# JTAG20M-STLV2.net
KiCad netlist of a schematic drawn in EAGLE
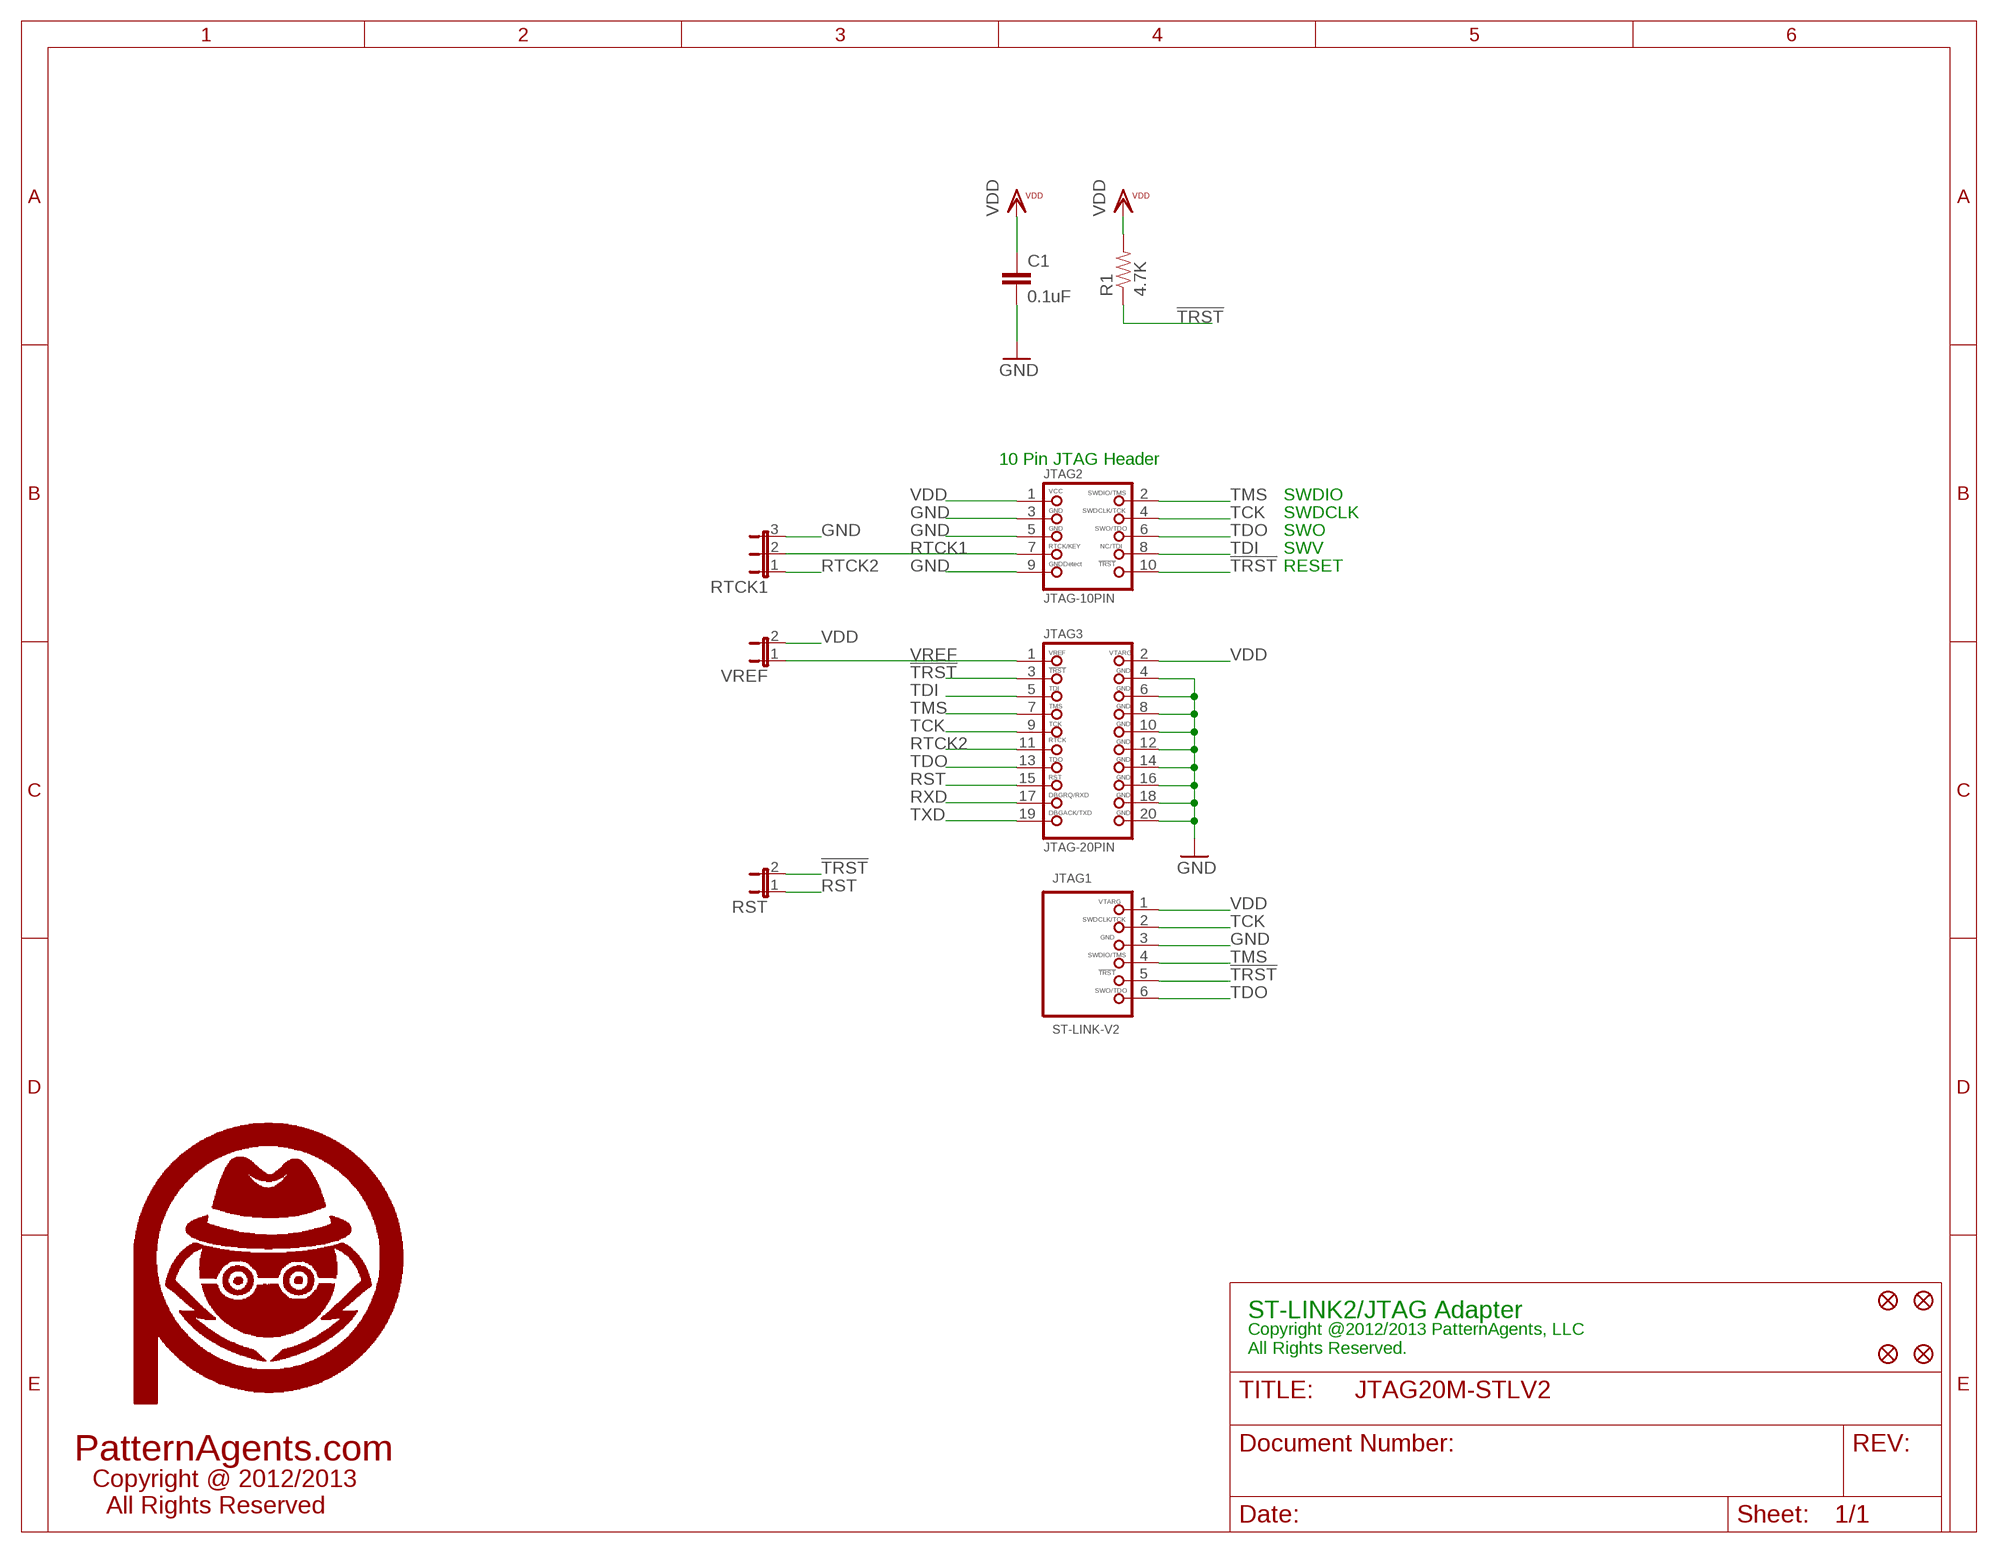
[diagram p0: schematic, sheet 1]

(export (version "E")
  (design (tool "Eeschema 10.0.6"))
  (components
    (comp (ref "C1")
      (value "0.1uF")
      (footprint "eagle-import:0603-CAP")
      (libsource (lib "eagle-import") (part "CAP0603-CAP"))
    )
    (comp (ref "FID1")
      (value "FIDUCIAL1.5X3")
      (footprint "eagle-import:FIDUCIAL-1.5X3")
      (libsource (lib "eagle-import") (part "FIDUCIAL1.5X3"))
    )
    (comp (ref "FID2")
      (value "FIDUCIAL1.5X3")
      (footprint "eagle-import:FIDUCIAL-1.5X3")
      (libsource (lib "eagle-import") (part "FIDUCIAL1.5X3"))
    )
    (comp (ref "FID3")
      (value "FIDUCIAL1.5X3")
      (footprint "eagle-import:FIDUCIAL-1.5X3")
      (libsource (lib "eagle-import") (part "FIDUCIAL1.5X3"))
    )
    (comp (ref "FID4")
      (value "FIDUCIAL1.5X3")
      (footprint "eagle-import:FIDUCIAL-1.5X3")
      (libsource (lib "eagle-import") (part "FIDUCIAL1.5X3"))
    )
    (comp (ref "JTAG1")
      (value "ST-LINK-V2")
      (footprint "eagle-import:1X06_2.54MM_PTH")
      (libsource (lib "eagle-import") (part "ST-LINK-V2"))
    )
    (comp (ref "JTAG2")
      (value "JTAG-10PIN")
      (footprint "eagle-import:2X05_1.27MM_SMT")
      (libsource (lib "eagle-import") (part "JTAG-10PINSMD"))
    )
    (comp (ref "JTAG3")
      (value "JTAG-20PIN")
      (footprint "eagle-import:2X10_2.54MM_PTH")
      (libsource (lib "eagle-import") (part "JTAG-20PIN"))
    )
    (comp (ref "R1")
      (value "4.7K")
      (footprint "eagle-import:0603-RES")
      (libsource (lib "eagle-import") (part "RESISTOR_SFE0603-RES"))
    )
    (comp (ref "RST")
      (value "JUMPER2")
      (footprint "eagle-import:JUMPER2")
      (libsource (lib "eagle-import") (part "JUMPER2"))
    )
    (comp (ref "RTCK1")
      (value "JUMPER3")
      (footprint "eagle-import:JUMPER3")
      (libsource (lib "eagle-import") (part "JUMPER3"))
    )
    (comp (ref "U$2")
      (value "PA_LOGO_SYMLARGE")
      (footprint "eagle-import:PA_LOGO_AGENT_LRG_SYM")
      (libsource (lib "eagle-import") (part "PA_LOGO_SYMLARGE"))
    )
    (comp (ref "VREF")
      (value "JUMPER2")
      (footprint "eagle-import:JUMPER2")
      (libsource (lib "eagle-import") (part "JUMPER2"))
    )
  )
  (nets
    (net (code "1") (name "/RST") (class "Default")
      (node (ref "JTAG3") (pin "15") (pinfunction "15_15") (pintype "passive"))
      (node (ref "RST") (pin "1") (pinfunction "1_1") (pintype "passive"))
    )
    (net (code "2") (name "/RTCK1") (class "Default")
      (node (ref "JTAG2") (pin "7") (pinfunction "7_7") (pintype "passive"))
      (node (ref "RTCK1") (pin "2") (pinfunction "2_2") (pintype "passive"))
    )
    (net (code "3") (name "/RTCK2") (class "Default")
      (node (ref "JTAG3") (pin "11") (pinfunction "11_11") (pintype "passive"))
      (node (ref "RTCK1") (pin "1") (pinfunction "1_1") (pintype "passive"))
    )
    (net (code "4") (name "/RXD") (class "Default")
      (node (ref "JTAG3") (pin "17") (pinfunction "17_17") (pintype "passive"))
    )
    (net (code "5") (name "/TCK") (class "Default")
      (node (ref "JTAG1") (pin "2") (pinfunction "2_2") (pintype "passive"))
      (node (ref "JTAG2") (pin "4") (pinfunction "4_4") (pintype "passive"))
      (node (ref "JTAG3") (pin "9") (pinfunction "9_9") (pintype "passive"))
    )
    (net (code "6") (name "/TDI") (class "Default")
      (node (ref "JTAG2") (pin "8") (pinfunction "8_8") (pintype "passive"))
      (node (ref "JTAG3") (pin "5") (pinfunction "5_5") (pintype "passive"))
    )
    (net (code "7") (name "/TDO") (class "Default")
      (node (ref "JTAG1") (pin "6") (pinfunction "6_6") (pintype "passive"))
      (node (ref "JTAG2") (pin "6") (pinfunction "6_6") (pintype "passive"))
      (node (ref "JTAG3") (pin "13") (pinfunction "13_13") (pintype "passive"))
    )
    (net (code "8") (name "/TMS") (class "Default")
      (node (ref "JTAG1") (pin "4") (pinfunction "4_4") (pintype "passive"))
      (node (ref "JTAG2") (pin "2") (pinfunction "2_2") (pintype "passive"))
      (node (ref "JTAG3") (pin "7") (pinfunction "7_7") (pintype "passive"))
    )
    (net (code "9") (name "/TXD") (class "Default")
      (node (ref "JTAG3") (pin "19") (pinfunction "19_19") (pintype "passive"))
    )
    (net (code "10") (name "/VREF") (class "Default")
      (node (ref "JTAG3") (pin "1") (pinfunction "1_1") (pintype "passive"))
      (node (ref "VREF") (pin "1") (pinfunction "1_1") (pintype "passive"))
    )
    (net (code "11") (name "/~{TRST}") (class "Default")
      (node (ref "JTAG1") (pin "5") (pinfunction "5_5") (pintype "passive"))
      (node (ref "JTAG2") (pin "10") (pinfunction "10_10") (pintype "passive"))
      (node (ref "JTAG3") (pin "3") (pinfunction "3_3") (pintype "passive"))
      (node (ref "R1") (pin "1") (pinfunction "1_1") (pintype "passive"))
      (node (ref "RST") (pin "2") (pinfunction "2_2") (pintype "passive"))
    )
    (net (code "12") (name "GND") (class "Default")
      (node (ref "C1") (pin "2") (pinfunction "2_2") (pintype "passive"))
      (node (ref "JTAG1") (pin "3") (pinfunction "3_3") (pintype "passive"))
      (node (ref "JTAG2") (pin "3") (pinfunction "3_3") (pintype "passive"))
      (node (ref "JTAG2") (pin "5") (pinfunction "5_5") (pintype "passive"))
      (node (ref "JTAG2") (pin "9") (pinfunction "9_9") (pintype "passive"))
      (node (ref "JTAG3") (pin "10") (pinfunction "10_10") (pintype "passive"))
      (node (ref "JTAG3") (pin "12") (pinfunction "12_12") (pintype "passive"))
      (node (ref "JTAG3") (pin "14") (pinfunction "14_14") (pintype "passive"))
      (node (ref "JTAG3") (pin "16") (pinfunction "16_16") (pintype "passive"))
      (node (ref "JTAG3") (pin "18") (pinfunction "18_18") (pintype "passive"))
      (node (ref "JTAG3") (pin "20") (pinfunction "20_20") (pintype "passive"))
      (node (ref "JTAG3") (pin "4") (pinfunction "4_4") (pintype "passive"))
      (node (ref "JTAG3") (pin "6") (pinfunction "6_6") (pintype "passive"))
      (node (ref "JTAG3") (pin "8") (pinfunction "8_8") (pintype "passive"))
      (node (ref "RTCK1") (pin "3") (pinfunction "3_3") (pintype "passive"))
    )
    (net (code "13") (name "VDD") (class "Default")
      (node (ref "C1") (pin "1") (pinfunction "1_1") (pintype "passive"))
      (node (ref "JTAG1") (pin "1") (pinfunction "1_1") (pintype "passive"))
      (node (ref "JTAG2") (pin "1") (pinfunction "1_1") (pintype "passive"))
      (node (ref "JTAG3") (pin "2") (pinfunction "2_2") (pintype "passive"))
      (node (ref "R1") (pin "2") (pinfunction "2_2") (pintype "passive"))
      (node (ref "VREF") (pin "2") (pinfunction "2_2") (pintype "passive"))
    )
  )
)
